# 3V3_LDO.net
KiCad netlist of a schematic drawn in Altium Designer
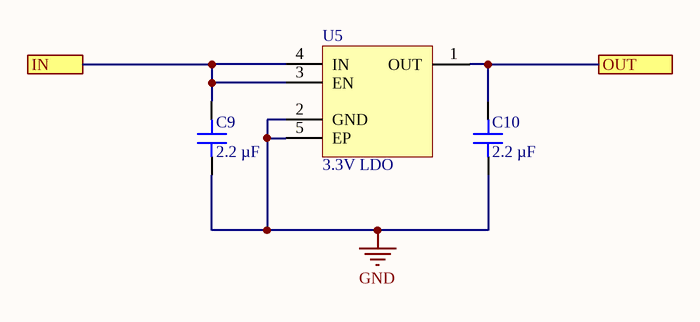
[diagram p0: 3V3_LDO.SchDoc]

(export (version "E")
  (design (tool "Eeschema 10.0.6"))
  (components
    (comp (ref "C9")
      (value "2.2 µF")
      (footprint "CAP 0402_1005")
      (description "CAP CER 0.1UF 16V X7R 0402")
      (fields (field (name "PART NUMBER") "C0402C104K4RACAUTO") (field (name "MANUFACTURER") "KEMET"))
      (libsource (lib "Celestial Altium Library - altium_library") (part "Capacitor"))
    )
    (comp (ref "C10")
      (value "2.2 µF")
      (footprint "CAP 0402_1005")
      (description "CAP CER 0.1UF 16V X7R 0402")
      (fields (field (name "PART NUMBER") "C0402C104K4RACAUTO") (field (name "MANUFACTURER") "KEMET"))
      (libsource (lib "Celestial Altium Library - altium_library") (part "Capacitor"))
    )
    (comp (ref "U5") (value "3.3V LDO") (footprint "XDFN-4") (libsource (lib "IC") (part "TLV74033PDQNR")))
  )
  (nets
    (net (code "1") (name "/IN") (class "Default")
      (node (ref "C9") (pin "2") (pinfunction "2_2") (pintype "passive"))
      (node (ref "U5") (pin "3") (pinfunction "EN_3") (pintype "passive"))
      (node (ref "U5") (pin "4") (pinfunction "IN_4") (pintype "passive"))
    )
    (net (code "2") (name "/OUT") (class "Default")
      (node (ref "C10") (pin "2") (pinfunction "2_2") (pintype "passive"))
      (node (ref "U5") (pin "1") (pinfunction "OUT_1") (pintype "passive"))
    )
    (net (code "3") (name "GND") (class "Default")
      (node (ref "C10") (pin "1") (pinfunction "1_1") (pintype "passive"))
      (node (ref "C9") (pin "1") (pinfunction "1_1") (pintype "passive"))
      (node (ref "U5") (pin "2") (pinfunction "GND_2") (pintype "passive"))
      (node (ref "U5") (pin "5") (pinfunction "EP_5") (pintype "passive"))
    )
  )
)
